# 2014-9-17.net
KiCad netlist of a schematic drawn in Altium Designer
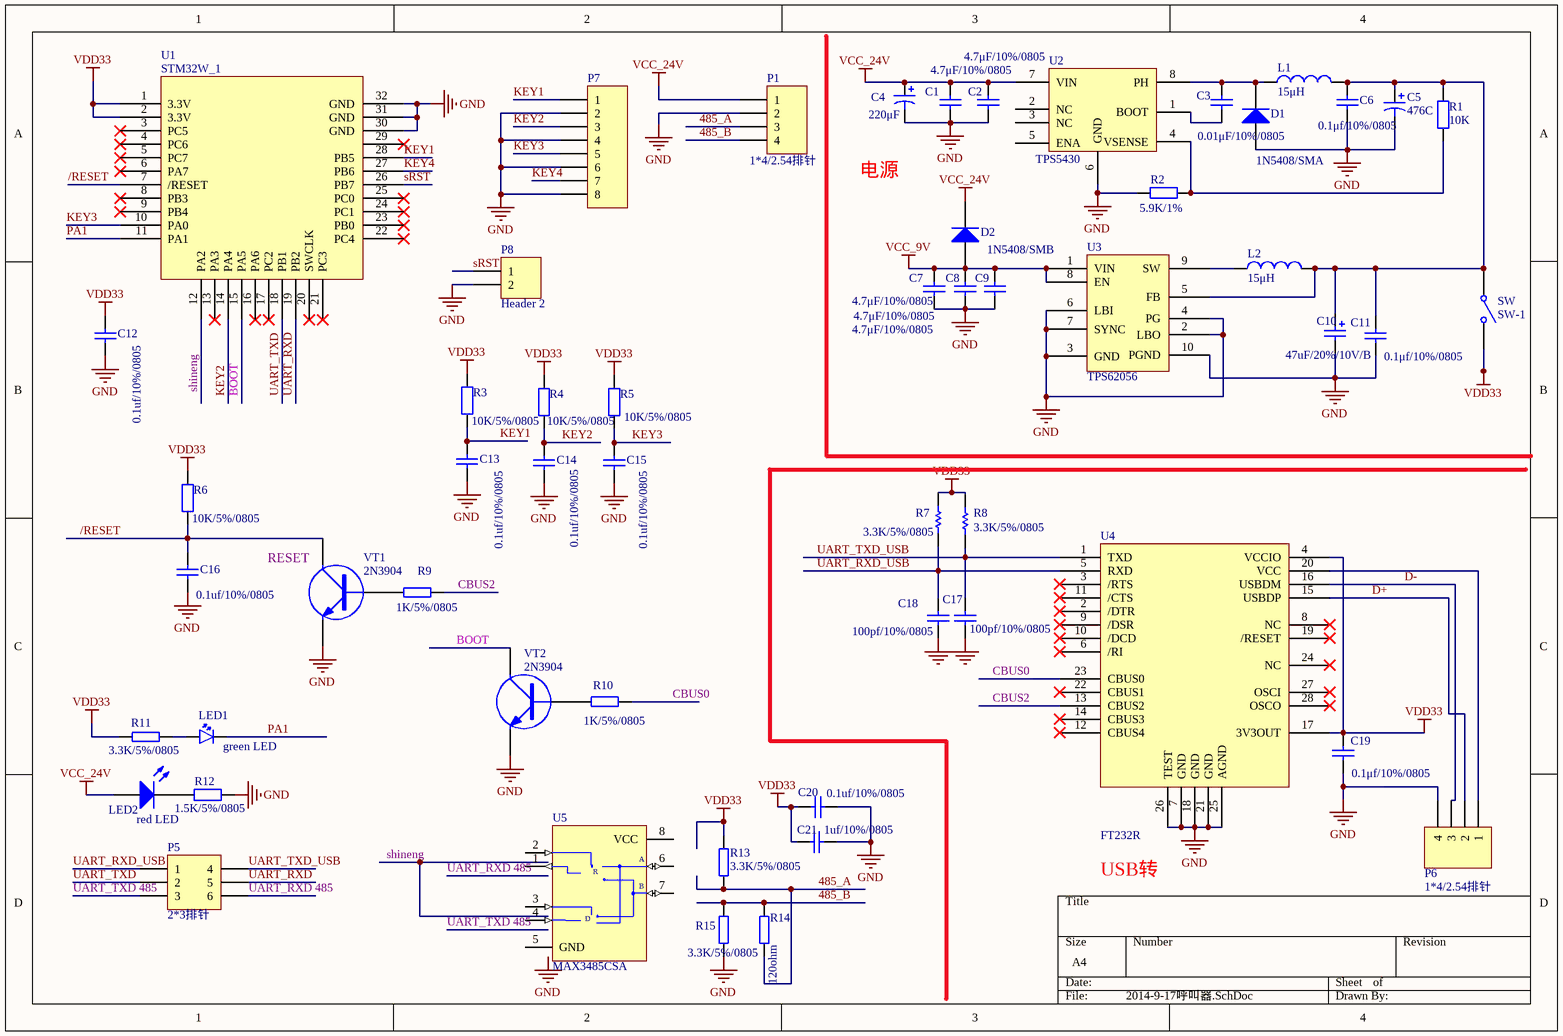
[diagram p0: 2014-9-17呼叫器.SchDoc]

(export (version "E")
  (design (tool "Eeschema 10.0.6"))
  (components
    (comp (ref "C1")
      (value "4.7μF/10%/0805")
      (footprint "C-0805")
      (description "Capacitor")
      (fields (field (name "PUBLISHER") "Altium Limited"))
      (libsource (lib "Miscellaneous Devices") (part "Cap"))
    )
    (comp (ref "C2")
      (value "4.7μF/10%/0805")
      (footprint "C-0805")
      (description "Capacitor")
      (fields (field (name "PUBLISHER") "Altium Limited"))
      (libsource (lib "Miscellaneous Devices") (part "Cap"))
    )
    (comp (ref "C3")
      (value "0.01μF/10%/0805")
      (footprint "C-0805")
      (description "Capacitor")
      (fields (field (name "PUBLISHER") "Altium Limited"))
      (libsource (lib "Miscellaneous Devices") (part "Cap"))
    )
    (comp (ref "C4")
      (value "220μF")
      (footprint "CZ3.0/6.5")
      (description "Polarized Capacitor (Radial)")
      (fields (field (name "PUBLISHER") "Altium Limited"))
      (libsource (lib "Miscellaneous Devices") (part "Cap Pol1"))
    )
    (comp (ref "C5")
      (value "476C")
      (footprint "C-TAN-D")
      (description "Polarized Capacitor (Radial)")
      (fields (field (name "PUBLISHER") "Altium Limited"))
      (libsource (lib "Miscellaneous Devices") (part "Cap Pol1"))
    )
    (comp (ref "C6")
      (value "0.1μf/10%/0805")
      (footprint "C-0805")
      (description "Capacitor")
      (fields (field (name "PUBLISHER") "Altium Limited"))
      (libsource (lib "Miscellaneous Devices") (part "Cap"))
    )
    (comp (ref "C7")
      (value "4.7μF/10%/0805")
      (footprint "C-0805")
      (description "Capacitor")
      (fields (field (name "PUBLISHER") "Altium Limited"))
      (libsource (lib "Miscellaneous Devices") (part "Cap"))
    )
    (comp (ref "C8")
      (value "4.7μF/10%/0805")
      (footprint "C-0805")
      (description "Capacitor")
      (fields (field (name "PUBLISHER") "Altium Limited"))
      (libsource (lib "Miscellaneous Devices") (part "Cap"))
    )
    (comp (ref "C9")
      (value "4.7μF/10%/0805")
      (footprint "C-0805")
      (description "Capacitor")
      (fields (field (name "PUBLISHER") "Altium Limited"))
      (libsource (lib "Miscellaneous Devices") (part "Cap"))
    )
    (comp (ref "C10")
      (value "47uF/20%/10V/B")
      (footprint "C-TAN-B")
      (libsource (lib "浙江关西电机数据库") (part "CAP_polarity"))
    )
    (comp (ref "C11")
      (value "0.1μf/10%/0805")
      (footprint "C-0805")
      (description "Capacitor")
      (fields (field (name "PUBLISHER") "Altium Limited"))
      (libsource (lib "Miscellaneous Devices") (part "Cap"))
    )
    (comp (ref "C12")
      (value "0.1uf/10%/0805")
      (footprint "C-0805")
      (description "Capacitor")
      (fields (field (name "PUBLISHER") "Altium Limited"))
      (libsource (lib "Miscellaneous Devices") (part "Cap"))
    )
    (comp (ref "C13")
      (value "0.1uf/10%/0805")
      (footprint "C-0805")
      (description "Capacitor")
      (fields (field (name "PUBLISHER") "Altium Limited"))
      (libsource (lib "Miscellaneous Devices") (part "Cap"))
    )
    (comp (ref "C14")
      (value "0.1uf/10%/0805")
      (footprint "C-0805")
      (description "Capacitor")
      (fields (field (name "PUBLISHER") "Altium Limited"))
      (libsource (lib "Miscellaneous Devices") (part "Cap"))
    )
    (comp (ref "C15")
      (value "0.1uf/10%/0805")
      (footprint "C-0805")
      (description "Capacitor")
      (fields (field (name "PUBLISHER") "Altium Limited"))
      (libsource (lib "Miscellaneous Devices") (part "Cap"))
    )
    (comp (ref "C16")
      (value "0.1uf/10%/0805")
      (footprint "C-0805")
      (description "Capacitor")
      (fields (field (name "PUBLISHER") "Altium Limited"))
      (libsource (lib "Miscellaneous Devices") (part "Cap"))
    )
    (comp (ref "C17")
      (value "100pf/10%/0805")
      (footprint "C-0805")
      (description "Capacitor")
      (fields (field (name "PUBLISHER") "Altium Limited"))
      (libsource (lib "Miscellaneous Devices") (part "Cap"))
    )
    (comp (ref "C18")
      (value "100pf/10%/0805")
      (footprint "C-0805")
      (description "Capacitor")
      (fields (field (name "PUBLISHER") "Altium Limited"))
      (libsource (lib "Miscellaneous Devices") (part "Cap"))
    )
    (comp (ref "C19")
      (value "0.1μf/10%/0805")
      (footprint "C-0805")
      (description "Capacitor")
      (fields (field (name "PUBLISHER") "Altium Limited"))
      (libsource (lib "Miscellaneous Devices") (part "Cap"))
    )
    (comp (ref "C20")
      (value "0.1uf/10%/0805")
      (footprint "C-0805")
      (description "Capacitor")
      (fields (field (name "PUBLISHER") "Altium Limited"))
      (libsource (lib "Miscellaneous Devices") (part "Cap"))
    )
    (comp (ref "C21")
      (value "1uf/10%/0805")
      (footprint "C-0805")
      (description "Capacitor")
      (fields (field (name "PUBLISHER") "Altium Limited"))
      (libsource (lib "Miscellaneous Devices") (part "Cap"))
    )
    (comp (ref "D1")
      (value "1N5408/SMA")
      (footprint "SMA 2+")
      (description "3 Amp Medium Power Silicon Rectifier Diode")
      (fields (field (name "PUBLISHER") "Altium Limited"))
      (libsource (lib "Miscellaneous Devices") (part "Diode 1N5408"))
    )
    (comp (ref "D2")
      (value "1N5408/SMB")
      (footprint "smb")
      (description "3 Amp Medium Power Silicon Rectifier Diode")
      (fields (field (name "PUBLISHER") "Altium Limited"))
      (libsource (lib "Miscellaneous Devices") (part "Diode 1N5408"))
    )
    (comp (ref "L1")
      (value "15μH")
      (footprint "GSDS104C2")
      (description "Inductor")
      (fields (field (name "PUBLISHER") "Altium Limited"))
      (libsource (lib "Miscellaneous Devices") (part "Inductor"))
    )
    (comp (ref "L2")
      (value "15μH")
      (footprint "GSDS104C2")
      (description "Inductor")
      (fields (field (name "PUBLISHER") "Altium Limited"))
      (libsource (lib "Miscellaneous Devices") (part "Inductor"))
    )
    (comp (ref "LED1") (value "green LED") (footprint "LED-φ3") (libsource (lib "Haze") (part "LED")))
    (comp (ref "LED2")
      (value "red LED")
      (footprint "LED-φ3")
      (description "Typical BLUE SiC LED")
      (fields (field (name "PUBLISHER") "Altium Limited"))
      (libsource (lib "Miscellaneous Devices") (part "LED3"))
    )
    (comp (ref "P1")
      (value "1*4/2.54排针")
      (footprint "PIN-S-2.54-1*4")
      (description "Header, 4-Pin")
      (fields (field (name "PUBLISHER") "Altium Limited"))
      (libsource (lib "Miscellaneous Connectors") (part "Header 4"))
    )
    (comp (ref "P5")
      (value "2*3排针")
      (footprint "HDR2X3_CEN")
      (description "Header, 3-Pin, Dual row")
      (fields (field (name "PUBLISHER") "Altium Limited"))
      (libsource (lib "Miscellaneous Connectors") (part "Header 3X2A"))
    )
    (comp (ref "P6")
      (value "1*4/2.54排针")
      (footprint "PIN-S-2.54-1*4")
      (description "Header, 4-Pin")
      (fields (field (name "PUBLISHER") "Altium Limited"))
      (libsource (lib "") (part "Header 4_1"))
    )
    (comp (ref "P7")
      (value "Header 8")
      (footprint "HDR1X8")
      (description "Header, 8-Pin")
      (fields (field (name "PUBLISHER") "Altium Limited"))
      (libsource (lib "Miscellaneous Connectors") (part "Header 8"))
    )
    (comp (ref "P8")
      (value "Header 2")
      (footprint "HDR1X2")
      (description "Header, 2-Pin")
      (fields (field (name "PUBLISHER") "Altium Limited"))
      (libsource (lib "Miscellaneous Connectors") (part "Header 2"))
    )
    (comp (ref "R1")
      (value "10K")
      (footprint "R-0805")
      (description "Resistor")
      (fields (field (name "PUBLISHER") "Altium Limited"))
      (libsource (lib "Miscellaneous Devices") (part "Res2"))
    )
    (comp (ref "R2")
      (value "5.9K/1%")
      (footprint "R-0805")
      (description "Resistor")
      (fields (field (name "PUBLISHER") "Altium Limited"))
      (libsource (lib "") (part "Res2_1"))
    )
    (comp (ref "R3")
      (value "10K/5%/0805")
      (footprint "R-0805")
      (description "Resistor")
      (fields (field (name "PUBLISHER") "Altium Limited"))
      (libsource (lib "Miscellaneous Devices") (part "Res2"))
    )
    (comp (ref "R4")
      (value "10K/5%/0805")
      (footprint "R-0805")
      (description "Resistor")
      (fields (field (name "PUBLISHER") "Altium Limited"))
      (libsource (lib "Miscellaneous Devices") (part "Res2"))
    )
    (comp (ref "R5")
      (value "10K/5%/0805")
      (footprint "R-0805")
      (description "Resistor")
      (fields (field (name "PUBLISHER") "Altium Limited"))
      (libsource (lib "Miscellaneous Devices") (part "Res2"))
    )
    (comp (ref "R6")
      (value "10K/5%/0805")
      (footprint "R-0805")
      (description "Resistor")
      (fields (field (name "PUBLISHER") "Altium Limited"))
      (libsource (lib "Miscellaneous Devices") (part "Res2"))
    )
    (comp (ref "R7")
      (value "3.3K/5%/0805")
      (footprint "R-0805")
      (libsource (lib "SCHLIBRARIES") (part "RES_1"))
    )
    (comp (ref "R8")
      (value "3.3K/5%/0805")
      (footprint "R-0805")
      (libsource (lib "SCHLIBRARIES") (part "RES_1"))
    )
    (comp (ref "R9")
      (value "1K/5%/0805")
      (footprint "R-0805")
      (description "R")
      (libsource (lib "Haze") (part "RES"))
    )
    (comp (ref "R10")
      (value "1K/5%/0805")
      (footprint "R-0805")
      (description "R")
      (libsource (lib "Haze") (part "RES"))
    )
    (comp (ref "R11")
      (value "3.3K/5%/0805")
      (footprint "R-0805")
      (description "R")
      (libsource (lib "Haze") (part "RES"))
    )
    (comp (ref "R12")
      (value "1.5K/5%/0805")
      (footprint "R-0805")
      (description "Resistor")
      (fields (field (name "PUBLISHER") "Altium Limited"))
      (libsource (lib "") (part "Res2_1"))
    )
    (comp (ref "R13")
      (value "3.3K/5%/0805")
      (footprint "R-0805")
      (description "R")
      (libsource (lib "Haze") (part "RES"))
    )
    (comp (ref "R14")
      (value "120ohm")
      (footprint "R-0805")
      (description "R")
      (libsource (lib "Haze") (part "RES"))
    )
    (comp (ref "R15")
      (value "3.3K/5%/0805")
      (footprint "R-0805")
      (description "R")
      (libsource (lib "Haze") (part "RES"))
    )
    (comp (ref "SW")
      (value "SW-1")
      (footprint "PIN-S-2.54-1*2")
      (libsource (lib "SCHLIBRARIES") (part "SW-1"))
    )
    (comp (ref "U1")
      (value "STM32W_1")
      (footprint "STM32W108-3")
      (libsource (lib "STM32W108-3") (part "STM32W108-3"))
    )
    (comp (ref "U2") (value "TPS5430") (footprint "SO-G8") (libsource (lib "SCHLIBRARIES") (part "TPS5430")))
    (comp (ref "U3")
      (value "TPS62056")
      (footprint "MSOP-10")
      (libsource (lib "SCHLIBRARIES") (part "TPS62056"))
    )
    (comp (ref "U4") (value "FT232R") (footprint "SSOP-28") (libsource (lib "Haze") (part "FT232R")))
    (comp (ref "U5")
      (value "MAX3485CSA")
      (footprint "SO-G8")
      (description "Low-Power, Slew-Rate-Limited RS-485/RS-422 Transceiver")
      (fields (field (name "PUBLISHER") "Altium Limited"))
      (libsource (lib "Maxim Communication Transceiver") (part "MAX485CSA"))
    )
    (comp (ref "VT1")
      (value "2N3904")
      (footprint "SOT23-3")
      (description "NPN Transistor")
      (libsource (lib "Haze") (part "NPN"))
    )
    (comp (ref "VT2")
      (value "2N3904")
      (footprint "SOT23-3")
      (description "NPN Transistor")
      (libsource (lib "Haze") (part "NPN"))
    )
  )
  (nets
    (net (code "1") (name "/485_A") (class "Default")
      (node (ref "P1") (pin "3") (pinfunction "3_3") (pintype "passive"))
      (node (ref "R13") (pin "1") (pinfunction "1_1") (pintype "passive"))
      (node (ref "R14") (pin "2") (pinfunction "2_2") (pintype "passive"))
    )
    (net (code "2") (name "/485_B") (class "Default")
      (node (ref "P1") (pin "4") (pinfunction "4_4") (pintype "passive"))
      (node (ref "R14") (pin "1") (pinfunction "1_1") (pintype "passive"))
      (node (ref "R15") (pin "2") (pinfunction "2_2") (pintype "passive"))
    )
    (net (code "3") (name "/BOOT") (class "Default")
      (node (ref "U1") (pin "15") (pinfunction "PA5_15") (pintype "passive"))
      (node (ref "VT2") (pin "3") (pinfunction "C_3") (pintype "passive"))
    )
    (net (code "4") (name "/CBUS0") (class "Default")
      (node (ref "R10") (pin "2") (pinfunction "2_2") (pintype "passive"))
      (node (ref "U4") (pin "23") (pinfunction "CBUS0_23") (pintype "passive"))
    )
    (net (code "5") (name "/CBUS2") (class "Default")
      (node (ref "R9") (pin "2") (pinfunction "2_2") (pintype "passive"))
      (node (ref "U4") (pin "13") (pinfunction "CBUS2_13") (pintype "passive"))
    )
    (net (code "6") (name "/D+") (class "Default")
      (node (ref "P6") (pin "2") (pinfunction "2_2") (pintype "passive"))
      (node (ref "U4") (pin "15") (pinfunction "USBDP_15") (pintype "passive"))
    )
    (net (code "7") (name "/D-") (class "Default")
      (node (ref "P6") (pin "3") (pinfunction "3_3") (pintype "passive"))
      (node (ref "U4") (pin "16") (pinfunction "USBDM_16") (pintype "passive"))
    )
    (net (code "8") (name "/KEY1") (class "Default")
      (node (ref "C13") (pin "2") (pinfunction "2_2") (pintype "passive"))
      (node (ref "P7") (pin "1") (pinfunction "1_1") (pintype "passive"))
      (node (ref "R3") (pin "1") (pinfunction "1_1") (pintype "passive"))
      (node (ref "U1") (pin "28") (pinfunction "PB5_28") (pintype "passive"))
    )
    (net (code "9") (name "/KEY2") (class "Default")
      (node (ref "C14") (pin "2") (pinfunction "2_2") (pintype "passive"))
      (node (ref "P7") (pin "3") (pinfunction "3_3") (pintype "passive"))
      (node (ref "R4") (pin "1") (pinfunction "1_1") (pintype "passive"))
      (node (ref "U1") (pin "14") (pinfunction "PA4_14") (pintype "passive"))
    )
    (net (code "10") (name "/KEY3") (class "Default")
      (node (ref "C15") (pin "2") (pinfunction "2_2") (pintype "passive"))
      (node (ref "P7") (pin "5") (pinfunction "5_5") (pintype "passive"))
      (node (ref "R5") (pin "1") (pinfunction "1_1") (pintype "passive"))
      (node (ref "U1") (pin "10") (pinfunction "PA0_10") (pintype "passive"))
    )
    (net (code "11") (name "/KEY4") (class "Default")
      (node (ref "P7") (pin "7") (pinfunction "7_7") (pintype "passive"))
      (node (ref "U1") (pin "27") (pinfunction "PB6_27") (pintype "passive"))
    )
    (net (code "12") (name "/PA1") (class "Default")
      (node (ref "LED1") (pin "2") (pinfunction "K_2") (pintype "passive"))
      (node (ref "U1") (pin "11") (pinfunction "PA1_11") (pintype "passive"))
    )
    (net (code "13") (name "/UART_RXD") (class "Default")
      (node (ref "P5") (pin "5") (pinfunction "5_5") (pintype "passive"))
      (node (ref "U1") (pin "19") (pinfunction "PB2_19") (pintype "passive"))
    )
    (net (code "14") (name "/UART_RXD 485") (class "Default")
      (node (ref "P5") (pin "6") (pinfunction "6_6") (pintype "passive"))
    )
    (net (code "15") (name "/UART_RXD_USB") (class "Default")
      (node (ref "C18") (pin "2") (pinfunction "2_2") (pintype "passive"))
      (node (ref "P5") (pin "1") (pinfunction "1_1") (pintype "passive"))
      (node (ref "R7") (pin "1") (pinfunction "1_1") (pintype "passive"))
      (node (ref "U4") (pin "5") (pinfunction "RXD_5") (pintype "passive"))
    )
    (net (code "16") (name "/UART_TXD") (class "Default")
      (node (ref "P5") (pin "2") (pinfunction "2_2") (pintype "passive"))
      (node (ref "U1") (pin "18") (pinfunction "PB1_18") (pintype "passive"))
    )
    (net (code "17") (name "/UART_TXD 485") (class "Default")
      (node (ref "P5") (pin "3") (pinfunction "3_3") (pintype "passive"))
    )
    (net (code "18") (name "/UART_TXD_USB") (class "Default")
      (node (ref "C17") (pin "2") (pinfunction "2_2") (pintype "passive"))
      (node (ref "P5") (pin "4") (pinfunction "4_4") (pintype "passive"))
      (node (ref "R8") (pin "1") (pinfunction "1_1") (pintype "passive"))
      (node (ref "U4") (pin "1") (pinfunction "TXD_1") (pintype "passive"))
    )
    (net (code "19") (name "/sRST") (class "Default")
      (node (ref "P8") (pin "1") (pinfunction "1_1") (pintype "passive"))
      (node (ref "U1") (pin "26") (pinfunction "PB7_26") (pintype "passive"))
    )
    (net (code "20") (name "/shineng") (class "Default")
      (node (ref "U1") (pin "12") (pinfunction "PA2_12") (pintype "passive"))
    )
    (net (code "21") (name "/{slash}RESET") (class "Default")
      (node (ref "C16") (pin "2") (pinfunction "2_2") (pintype "passive"))
      (node (ref "R6") (pin "1") (pinfunction "1_1") (pintype "passive"))
      (node (ref "U1") (pin "7") (pinfunction "/RESET_7") (pintype "passive"))
      (node (ref "VT1") (pin "3") (pinfunction "C_3") (pintype "passive"))
    )
    (net (code "22") (name "GND") (class "Default")
      (node (ref "C1") (pin "1") (pinfunction "1_1") (pintype "passive"))
      (node (ref "C10") (pin "2") (pinfunction "2_2") (pintype "passive"))
      (node (ref "C11") (pin "1") (pinfunction "1_1") (pintype "passive"))
      (node (ref "C12") (pin "1") (pinfunction "1_1") (pintype "passive"))
      (node (ref "C13") (pin "1") (pinfunction "1_1") (pintype "passive"))
      (node (ref "C14") (pin "1") (pinfunction "1_1") (pintype "passive"))
      (node (ref "C15") (pin "1") (pinfunction "1_1") (pintype "passive"))
      (node (ref "C16") (pin "1") (pinfunction "1_1") (pintype "passive"))
      (node (ref "C17") (pin "1") (pinfunction "1_1") (pintype "passive"))
      (node (ref "C18") (pin "1") (pinfunction "1_1") (pintype "passive"))
      (node (ref "C19") (pin "1") (pinfunction "1_1") (pintype "passive"))
      (node (ref "C2") (pin "1") (pinfunction "1_1") (pintype "passive"))
      (node (ref "C20") (pin "1") (pinfunction "1_1") (pintype "passive"))
      (node (ref "C21") (pin "1") (pinfunction "1_1") (pintype "passive"))
      (node (ref "C4") (pin "2") (pinfunction "2_2") (pintype "passive"))
      (node (ref "C5") (pin "2") (pinfunction "2_2") (pintype "passive"))
      (node (ref "C6") (pin "1") (pinfunction "1_1") (pintype "passive"))
      (node (ref "C7") (pin "1") (pinfunction "1_1") (pintype "passive"))
      (node (ref "C8") (pin "1") (pinfunction "1_1") (pintype "passive"))
      (node (ref "C9") (pin "1") (pinfunction "1_1") (pintype "passive"))
      (node (ref "D1") (pin "1") (pinfunction "A_1") (pintype "passive"))
      (node (ref "P1") (pin "2") (pinfunction "2_2") (pintype "passive"))
      (node (ref "P6") (pin "4") (pinfunction "4_4") (pintype "passive"))
      (node (ref "P7") (pin "2") (pinfunction "2_2") (pintype "passive"))
      (node (ref "P7") (pin "4") (pinfunction "4_4") (pintype "passive"))
      (node (ref "P7") (pin "6") (pinfunction "6_6") (pintype "passive"))
      (node (ref "P7") (pin "8") (pinfunction "8_8") (pintype "passive"))
      (node (ref "P8") (pin "2") (pinfunction "2_2") (pintype "passive"))
      (node (ref "R12") (pin "1") (pinfunction "1_1") (pintype "passive"))
      (node (ref "R15") (pin "1") (pinfunction "1_1") (pintype "passive"))
      (node (ref "R2") (pin "2") (pinfunction "2_2") (pintype "passive"))
      (node (ref "U1") (pin "30") (pinfunction "GND_30") (pintype "passive"))
      (node (ref "U1") (pin "31") (pinfunction "GND_31") (pintype "passive"))
      (node (ref "U1") (pin "32") (pinfunction "GND_32") (pintype "passive"))
      (node (ref "U2") (pin "6") (pinfunction "GND_6") (pintype "passive"))
      (node (ref "U3") (pin "10") (pinfunction "PGND_10") (pintype "passive"))
      (node (ref "U3") (pin "2") (pinfunction "LBO_2") (pintype "passive"))
      (node (ref "U3") (pin "3") (pinfunction "GND_3") (pintype "passive"))
      (node (ref "U3") (pin "4") (pinfunction "PG_4") (pintype "passive"))
      (node (ref "U3") (pin "6") (pinfunction "LBI_6") (pintype "passive"))
      (node (ref "U3") (pin "7") (pinfunction "SYNC_7") (pintype "passive"))
      (node (ref "U4") (pin "18") (pinfunction "GND_18") (pintype "passive"))
      (node (ref "U4") (pin "21") (pinfunction "GND_21") (pintype "passive"))
      (node (ref "U4") (pin "25") (pinfunction "AGND_25") (pintype "passive"))
      (node (ref "U4") (pin "26") (pinfunction "TEST_26") (pintype "passive"))
      (node (ref "U4") (pin "7") (pinfunction "GND_7") (pintype "passive"))
      (node (ref "VT1") (pin "2") (pinfunction "E_2") (pintype "passive"))
      (node (ref "VT2") (pin "2") (pinfunction "E_2") (pintype "passive"))
    )
    (net (code "23") (name "Net-(D1-K)") (class "Default")
      (node (ref "C3") (pin "2") (pinfunction "2_2") (pintype "passive"))
      (node (ref "D1") (pin "2") (pinfunction "K_2") (pintype "passive"))
      (node (ref "L1") (pin "1") (pinfunction "1_1") (pintype "passive"))
      (node (ref "U2") (pin "8") (pinfunction "PH_8") (pintype "passive"))
    )
    (net (code "24") (name "Net-(LED1-A)") (class "Default")
      (node (ref "LED1") (pin "1") (pinfunction "A_1") (pintype "passive"))
      (node (ref "R11") (pin "2") (pinfunction "2_2") (pintype "passive"))
    )
    (net (code "25") (name "Net-(LED2-K)") (class "Default")
      (node (ref "LED2") (pin "2") (pinfunction "K_2") (pintype "passive"))
      (node (ref "R12") (pin "2") (pinfunction "2_2") (pintype "passive"))
    )
    (net (code "26") (name "Net-(U2-BOOT)") (class "Default")
      (node (ref "C3") (pin "1") (pinfunction "1_1") (pintype "passive"))
      (node (ref "U2") (pin "1") (pinfunction "BOOT_1") (pintype "passive"))
    )
    (net (code "27") (name "Net-(U2-VSENSE)") (class "Default")
      (node (ref "R1") (pin "1") (pinfunction "1_1") (pintype "passive"))
      (node (ref "R2") (pin "1") (pinfunction "1_1") (pintype "passive"))
      (node (ref "U2") (pin "4") (pinfunction "VSENSE_4") (pintype "passive"))
    )
    (net (code "28") (name "Net-(U3-FB)") (class "Default")
      (node (ref "C10") (pin "1") (pinfunction "1_1") (pintype "passive"))
      (node (ref "C11") (pin "2") (pinfunction "2_2") (pintype "passive"))
      (node (ref "C5") (pin "1") (pinfunction "1_1") (pintype "passive"))
      (node (ref "C6") (pin "2") (pinfunction "2_2") (pintype "passive"))
      (node (ref "L1") (pin "2") (pinfunction "2_2") (pintype "passive"))
      (node (ref "L2") (pin "2") (pinfunction "2_2") (pintype "passive"))
      (node (ref "R1") (pin "2") (pinfunction "2_2") (pintype "passive"))
      (node (ref "SW") (pin "1") (pinfunction "1_1") (pintype "passive"))
      (node (ref "U3") (pin "5") (pinfunction "FB_5") (pintype "passive"))
    )
    (net (code "29") (name "Net-(U3-SW)") (class "Default")
      (node (ref "L2") (pin "1") (pinfunction "1_1") (pintype "passive"))
      (node (ref "U3") (pin "9") (pinfunction "SW_9") (pintype "passive"))
    )
    (net (code "30") (name "Net-(U4-VCC)") (class "Default")
      (node (ref "P6") (pin "1") (pinfunction "1_1") (pintype "passive"))
      (node (ref "U4") (pin "20") (pinfunction "VCC_20") (pintype "passive"))
    )
    (net (code "31") (name "Net-(VT1-B)") (class "Default")
      (node (ref "R9") (pin "1") (pinfunction "1_1") (pintype "passive"))
      (node (ref "VT1") (pin "1") (pinfunction "B_1") (pintype "passive"))
    )
    (net (code "32") (name "Net-(VT2-B)") (class "Default")
      (node (ref "R10") (pin "1") (pinfunction "1_1") (pintype "passive"))
      (node (ref "VT2") (pin "1") (pinfunction "B_1") (pintype "passive"))
    )
    (net (code "33") (name "VCC_9V") (class "Default")
      (node (ref "C7") (pin "2") (pinfunction "2_2") (pintype "passive"))
      (node (ref "C8") (pin "2") (pinfunction "2_2") (pintype "passive"))
      (node (ref "C9") (pin "2") (pinfunction "2_2") (pintype "passive"))
      (node (ref "D2") (pin "1") (pinfunction "A_1") (pintype "passive"))
      (node (ref "U3") (pin "1") (pinfunction "VIN_1") (pintype "passive"))
      (node (ref "U3") (pin "8") (pinfunction "EN_8") (pintype "passive"))
    )
    (net (code "34") (name "VCC_24V") (class "Default")
      (node (ref "C1") (pin "2") (pinfunction "2_2") (pintype "passive"))
      (node (ref "C2") (pin "2") (pinfunction "2_2") (pintype "passive"))
      (node (ref "C4") (pin "1") (pinfunction "1_1") (pintype "passive"))
      (node (ref "D2") (pin "2") (pinfunction "K_2") (pintype "passive"))
      (node (ref "LED2") (pin "1") (pinfunction "A_1") (pintype "passive"))
      (node (ref "P1") (pin "1") (pinfunction "1_1") (pintype "passive"))
      (node (ref "U2") (pin "7") (pinfunction "VIN_7") (pintype "passive"))
    )
    (net (code "35") (name "VDD33") (class "Default")
      (node (ref "C12") (pin "2") (pinfunction "2_2") (pintype "passive"))
      (node (ref "C19") (pin "2") (pinfunction "2_2") (pintype "passive"))
      (node (ref "C20") (pin "2") (pinfunction "2_2") (pintype "passive"))
      (node (ref "C21") (pin "2") (pinfunction "2_2") (pintype "passive"))
      (node (ref "R11") (pin "1") (pinfunction "1_1") (pintype "passive"))
      (node (ref "R13") (pin "2") (pinfunction "2_2") (pintype "passive"))
      (node (ref "R3") (pin "2") (pinfunction "2_2") (pintype "passive"))
      (node (ref "R4") (pin "2") (pinfunction "2_2") (pintype "passive"))
      (node (ref "R5") (pin "2") (pinfunction "2_2") (pintype "passive"))
      (node (ref "R6") (pin "2") (pinfunction "2_2") (pintype "passive"))
      (node (ref "R7") (pin "2") (pinfunction "2_2") (pintype "passive"))
      (node (ref "R8") (pin "2") (pinfunction "2_2") (pintype "passive"))
      (node (ref "SW") (pin "2") (pinfunction "2_2") (pintype "passive"))
      (node (ref "U1") (pin "1") (pinfunction "3.3V_1") (pintype "passive"))
      (node (ref "U1") (pin "2") (pinfunction "3.3V_2") (pintype "passive"))
      (node (ref "U4") (pin "17") (pinfunction "3V3OUT_17") (pintype "passive"))
      (node (ref "U4") (pin "4") (pinfunction "VCCIO_4") (pintype "passive"))
    )
    (net (code "36") (name "unconnected-(U1-PA3-Pad13)") (class "Default")
      (node (ref "U1") (pin "13") (pinfunction "PA3_13") (pintype "passive+no_connect"))
    )
    (net (code "37") (name "unconnected-(U1-PA6-Pad16)") (class "Default")
      (node (ref "U1") (pin "16") (pinfunction "PA6_16") (pintype "passive+no_connect"))
    )
    (net (code "38") (name "unconnected-(U1-PA7-Pad6)") (class "Default")
      (node (ref "U1") (pin "6") (pinfunction "PA7_6") (pintype "passive+no_connect"))
    )
    (net (code "39") (name "unconnected-(U1-PB0-Pad23)") (class "Default")
      (node (ref "U1") (pin "23") (pinfunction "PB0_23") (pintype "passive+no_connect"))
    )
    (net (code "40") (name "unconnected-(U1-PB3-Pad8)") (class "Default")
      (node (ref "U1") (pin "8") (pinfunction "PB3_8") (pintype "passive+no_connect"))
    )
    (net (code "41") (name "unconnected-(U1-PB4-Pad9)") (class "Default")
      (node (ref "U1") (pin "9") (pinfunction "PB4_9") (pintype "passive+no_connect"))
    )
    (net (code "42") (name "unconnected-(U1-PC0-Pad25)") (class "Default")
      (node (ref "U1") (pin "25") (pinfunction "PC0_25") (pintype "passive+no_connect"))
    )
    (net (code "43") (name "unconnected-(U1-PC1-Pad24)") (class "Default")
      (node (ref "U1") (pin "24") (pinfunction "PC1_24") (pintype "passive+no_connect"))
    )
    (net (code "44") (name "unconnected-(U1-PC2-Pad17)") (class "Default")
      (node (ref "U1") (pin "17") (pinfunction "PC2_17") (pintype "passive+no_connect"))
    )
    (net (code "45") (name "unconnected-(U1-PC3-Pad21)") (class "Default")
      (node (ref "U1") (pin "21") (pinfunction "PC3_21") (pintype "passive+no_connect"))
    )
    (net (code "46") (name "unconnected-(U1-PC4-Pad22)") (class "Default")
      (node (ref "U1") (pin "22") (pinfunction "PC4_22") (pintype "passive+no_connect"))
    )
    (net (code "47") (name "unconnected-(U1-PC5-Pad3)") (class "Default")
      (node (ref "U1") (pin "3") (pinfunction "PC5_3") (pintype "passive+no_connect"))
    )
    (net (code "48") (name "unconnected-(U1-PC6-Pad4)") (class "Default")
      (node (ref "U1") (pin "4") (pinfunction "PC6_4") (pintype "passive+no_connect"))
    )
    (net (code "49") (name "unconnected-(U1-PC7-Pad5)") (class "Default")
      (node (ref "U1") (pin "5") (pinfunction "PC7_5") (pintype "passive+no_connect"))
    )
    (net (code "50") (name "unconnected-(U1-Pad29)") (class "Default")
      (node (ref "U1") (pin "29") (pintype "passive+no_connect"))
    )
    (net (code "51") (name "unconnected-(U1-SWCLK-Pad20)") (class "Default")
      (node (ref "U1") (pin "20") (pinfunction "SWCLK_20") (pintype "passive+no_connect"))
    )
    (net (code "52") (name "unconnected-(U2-ENA-Pad5)") (class "Default")
      (node (ref "U2") (pin "5") (pinfunction "ENA_5") (pintype "passive"))
    )
    (net (code "53") (name "unconnected-(U2-NC-Pad2)") (class "Default")
      (node (ref "U2") (pin "2") (pinfunction "NC_2") (pintype "passive"))
    )
    (net (code "54") (name "unconnected-(U2-NC-Pad3)") (class "Default")
      (node (ref "U2") (pin "3") (pinfunction "NC_3") (pintype "passive"))
    )
    (net (code "55") (name "unconnected-(U4-CBUS1-Pad22)") (class "Default")
      (node (ref "U4") (pin "22") (pinfunction "CBUS1_22") (pintype "passive+no_connect"))
    )
    (net (code "56") (name "unconnected-(U4-CBUS3-Pad14)") (class "Default")
      (node (ref "U4") (pin "14") (pinfunction "CBUS3_14") (pintype "passive+no_connect"))
    )
    (net (code "57") (name "unconnected-(U4-CBUS4-Pad12)") (class "Default")
      (node (ref "U4") (pin "12") (pinfunction "CBUS4_12") (pintype "passive+no_connect"))
    )
    (net (code "58") (name "unconnected-(U4-NC-Pad8)") (class "Default")
      (node (ref "U4") (pin "8") (pinfunction "NC_8") (pintype "passive+no_connect"))
    )
    (net (code "59") (name "unconnected-(U4-NC-Pad24)") (class "Default")
      (node (ref "U4") (pin "24") (pinfunction "NC_24") (pintype "passive+no_connect"))
    )
    (net (code "60") (name "unconnected-(U4-OSCI-Pad27)") (class "Default")
      (node (ref "U4") (pin "27") (pinfunction "OSCI_27") (pintype "passive+no_connect"))
    )
    (net (code "61") (name "unconnected-(U4-OSCO-Pad28)") (class "Default")
      (node (ref "U4") (pin "28") (pinfunction "OSCO_28") (pintype "passive+no_connect"))
    )
    (net (code "62") (name "unconnected-(U4-{slash}CTS-Pad11)") (class "Default")
      (node (ref "U4") (pin "11") (pinfunction "/CTS_11") (pintype "passive+no_connect"))
    )
    (net (code "63") (name "unconnected-(U4-{slash}DCD-Pad10)") (class "Default")
      (node (ref "U4") (pin "10") (pinfunction "/DCD_10") (pintype "passive+no_connect"))
    )
    (net (code "64") (name "unconnected-(U4-{slash}DSR-Pad9)") (class "Default")
      (node (ref "U4") (pin "9") (pinfunction "/DSR_9") (pintype "passive+no_connect"))
    )
    (net (code "65") (name "unconnected-(U4-{slash}DTR-Pad2)") (class "Default")
      (node (ref "U4") (pin "2") (pinfunction "/DTR_2") (pintype "passive+no_connect"))
    )
    (net (code "66") (name "unconnected-(U4-{slash}RESET-Pad19)") (class "Default")
      (node (ref "U4") (pin "19") (pinfunction "/RESET_19") (pintype "passive+no_connect"))
    )
    (net (code "67") (name "unconnected-(U4-{slash}RI-Pad6)") (class "Default")
      (node (ref "U4") (pin "6") (pinfunction "/RI_6") (pintype "passive+no_connect"))
    )
    (net (code "68") (name "unconnected-(U4-{slash}RTS-Pad3)") (class "Default")
      (node (ref "U4") (pin "3") (pinfunction "/RTS_3") (pintype "passive+no_connect"))
    )
    (net (code "69") (name "unconnected-(U5-A-Pad6)") (class "Default")
      (node (ref "U5") (pin "6") (pinfunction "A_6") (pintype "bidirectional"))
    )
    (net (code "70") (name "unconnected-(U5-B-Pad7)") (class "Default")
      (node (ref "U5") (pin "7") (pinfunction "B_7") (pintype "bidirectional"))
    )
    (net (code "71") (name "unconnected-(U5-DE-Pad3)") (class "Default")
      (node (ref "U5") (pin "3") (pinfunction "DE_3") (pintype "input"))
    )
    (net (code "72") (name "unconnected-(U5-DI-Pad4)") (class "Default")
      (node (ref "U5") (pin "4") (pinfunction "DI_4") (pintype "input"))
    )
    (net (code "73") (name "unconnected-(U5-GND-Pad5)") (class "Default")
      (node (ref "U5") (pin "5") (pinfunction "GND_5") (pintype "power_in"))
    )
    (net (code "74") (name "unconnected-(U5-RO-Pad1)") (class "Default")
      (node (ref "U5") (pin "1") (pinfunction "RO_1") (pintype "output"))
    )
    (net (code "75") (name "unconnected-(U5-VCC-Pad8)") (class "Default")
      (node (ref "U5") (pin "8") (pinfunction "VCC_8") (pintype "power_in"))
    )
    (net (code "76") (name "unconnected-(U5-~{RE}-Pad2)") (class "Default")
      (node (ref "U5") (pin "2") (pinfunction "~{RE}_2") (pintype "input"))
    )
  )
)
